# BadgeHighSchoolFirst2.net
KiCad netlist of a schematic drawn in EAGLE
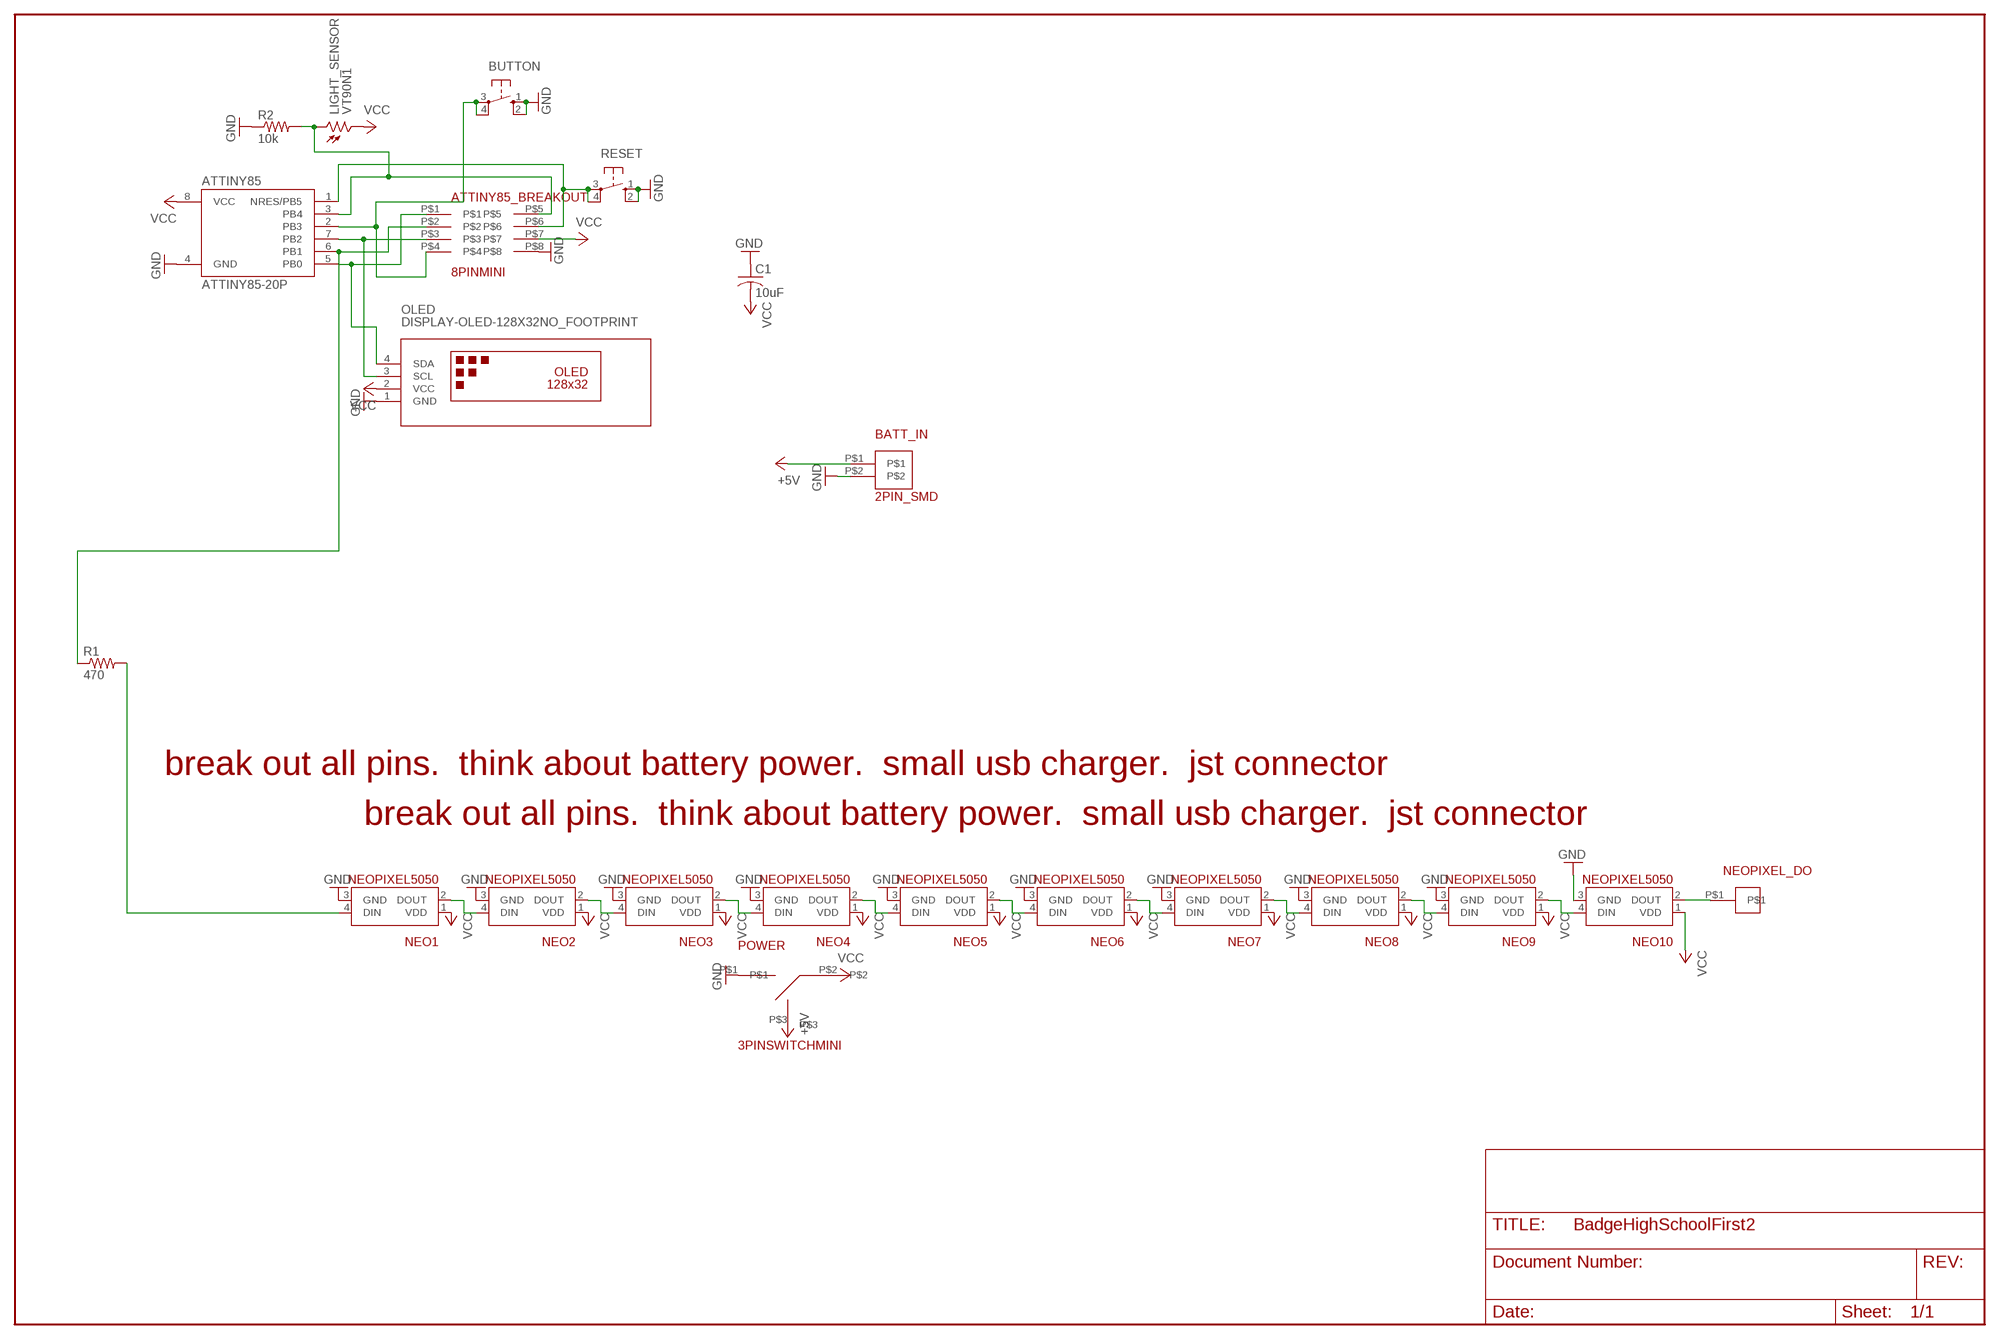
[diagram p0: schematic, sheet 1]

(export (version "E")
  (design (tool "Eeschema 10.0.6"))
  (components
    (comp (ref "ATTINY85")
      (value "ATTINY85-20P")
      (footprint "eagle-import:PDIP08_300MIL")
      (libsource (lib "eagle-import") (part "ATTINY85P-20"))
    )
    (comp (ref "ATTINY85_BREAKOUT")
      (value "8PINMINI")
      (footprint "eagle-import:8PINMINI")
      (libsource (lib "eagle-import") (part "8PINMINI"))
    )
    (comp (ref "BATT_IN")
      (value "2PIN_SMD")
      (footprint "eagle-import:2PIN_SMD")
      (libsource (lib "eagle-import") (part "2PIN_SMD"))
    )
    (comp (ref "BUTTON")
      (value "10-XX")
      (footprint "eagle-import:B3F-10XX")
      (fields (field (name "MPN") "B3F-1000"))
      (libsource (lib "eagle-import") (part "10-XX"))
    )
    (comp (ref "C1")
      (value "10uF")
      (footprint "eagle-import:C025-024X044")
      (libsource (lib "eagle-import") (part "C-US025-024X044"))
    )
    (comp (ref "LIGHT_SENSOR")
      (value "VT90N1")
      (footprint "eagle-import:VT900")
      (libsource (lib "eagle-import") (part "VT90N1"))
    )
    (comp (ref "NEO1")
      (value "NEOPIXEL5050")
      (footprint "eagle-import:NEOPIXEL5050")
      (libsource (lib "eagle-import") (part "NEOPIXEL5050"))
    )
    (comp (ref "NEO2")
      (value "NEOPIXEL5050")
      (footprint "eagle-import:NEOPIXEL5050")
      (libsource (lib "eagle-import") (part "NEOPIXEL5050"))
    )
    (comp (ref "NEO3")
      (value "NEOPIXEL5050")
      (footprint "eagle-import:NEOPIXEL5050")
      (libsource (lib "eagle-import") (part "NEOPIXEL5050"))
    )
    (comp (ref "NEO4")
      (value "NEOPIXEL5050")
      (footprint "eagle-import:NEOPIXEL5050")
      (libsource (lib "eagle-import") (part "NEOPIXEL5050"))
    )
    (comp (ref "NEO5")
      (value "NEOPIXEL5050")
      (footprint "eagle-import:NEOPIXEL5050")
      (libsource (lib "eagle-import") (part "NEOPIXEL5050"))
    )
    (comp (ref "NEO6")
      (value "NEOPIXEL5050")
      (footprint "eagle-import:NEOPIXEL5050")
      (libsource (lib "eagle-import") (part "NEOPIXEL5050"))
    )
    (comp (ref "NEO7")
      (value "NEOPIXEL5050")
      (footprint "eagle-import:NEOPIXEL5050")
      (libsource (lib "eagle-import") (part "NEOPIXEL5050"))
    )
    (comp (ref "NEO8")
      (value "NEOPIXEL5050")
      (footprint "eagle-import:NEOPIXEL5050")
      (libsource (lib "eagle-import") (part "NEOPIXEL5050"))
    )
    (comp (ref "NEO9")
      (value "NEOPIXEL5050")
      (footprint "eagle-import:NEOPIXEL5050")
      (libsource (lib "eagle-import") (part "NEOPIXEL5050"))
    )
    (comp (ref "NEO10")
      (value "NEOPIXEL5050")
      (footprint "eagle-import:NEOPIXEL5050")
      (libsource (lib "eagle-import") (part "NEOPIXEL5050"))
    )
    (comp (ref "NEOPIXEL_DO")
      (value "1PINMINI")
      (footprint "eagle-import:1PINMINI")
      (libsource (lib "eagle-import") (part "1PINMINI"))
    )
    (comp (ref "OLED")
      (value "DISPLAY-OLED-128X32NO_FOOTPRINT")
      (footprint "eagle-import:DISPLAY-OLED-128X32_NO_FOOTPRINT")
      (libsource (lib "eagle-import") (part "DISPLAY-OLED-128X32NO_FOOTPRINT"))
    )
    (comp (ref "POWER")
      (value "3PINSWITCHMINI")
      (footprint "eagle-import:3PINMINI")
      (libsource (lib "eagle-import") (part "3PINSWITCHMINI"))
    )
    (comp (ref "R1")
      (value "470")
      (footprint "eagle-import:0204_5")
      (libsource (lib "eagle-import") (part "R-US_0204/5"))
    )
    (comp (ref "R2")
      (value "10k")
      (footprint "eagle-import:0204_5")
      (libsource (lib "eagle-import") (part "R-US_0204/5"))
    )
    (comp (ref "RESET")
      (value "10-XX")
      (footprint "eagle-import:B3F-10XX")
      (fields (field (name "MPN") "B3F-1000"))
      (libsource (lib "eagle-import") (part "10-XX"))
    )
  )
  (nets
    (net (code "1") (name "+5V") (class "Default")
      (node (ref "BATT_IN") (pin "P$1") (pinfunction "P$1_P$1") (pintype "bidirectional"))
      (node (ref "POWER") (pin "P$3") (pinfunction "P$3_P$3") (pintype "bidirectional"))
    )
    (net (code "2") (name "GND") (class "Default")
      (node (ref "ATTINY85") (pin "4") (pinfunction "GND_4") (pintype "power_in"))
      (node (ref "ATTINY85_BREAKOUT") (pin "P$8") (pinfunction "P$8_P$8") (pintype "bidirectional"))
      (node (ref "BATT_IN") (pin "P$2") (pinfunction "P$2_P$2") (pintype "bidirectional"))
      (node (ref "BUTTON") (pin "1") (pinfunction "S_1") (pintype "passive"))
      (node (ref "BUTTON") (pin "2") (pinfunction "S1_2") (pintype "passive"))
      (node (ref "C1") (pin "1") (pinfunction "1_1") (pintype "passive"))
      (node (ref "NEO1") (pin "3") (pinfunction "GND_3") (pintype "bidirectional"))
      (node (ref "NEO10") (pin "3") (pinfunction "GND_3") (pintype "bidirectional"))
      (node (ref "NEO2") (pin "3") (pinfunction "GND_3") (pintype "bidirectional"))
      (node (ref "NEO3") (pin "3") (pinfunction "GND_3") (pintype "bidirectional"))
      (node (ref "NEO4") (pin "3") (pinfunction "GND_3") (pintype "bidirectional"))
      (node (ref "NEO5") (pin "3") (pinfunction "GND_3") (pintype "bidirectional"))
      (node (ref "NEO6") (pin "3") (pinfunction "GND_3") (pintype "bidirectional"))
      (node (ref "NEO7") (pin "3") (pinfunction "GND_3") (pintype "bidirectional"))
      (node (ref "NEO8") (pin "3") (pinfunction "GND_3") (pintype "bidirectional"))
      (node (ref "NEO9") (pin "3") (pinfunction "GND_3") (pintype "bidirectional"))
      (node (ref "OLED") (pin "1") (pinfunction "GND_1") (pintype "power_in"))
      (node (ref "POWER") (pin "P$1") (pinfunction "P$1_P$1") (pintype "bidirectional"))
      (node (ref "R2") (pin "1") (pinfunction "1_1") (pintype "passive"))
      (node (ref "RESET") (pin "1") (pinfunction "S_1") (pintype "passive"))
      (node (ref "RESET") (pin "2") (pinfunction "S1_2") (pintype "passive"))
    )
    (net (code "3") (name "Net-(ATTINY85-NRES{slash}PB5)") (class "Default")
      (node (ref "ATTINY85") (pin "1") (pinfunction "NRES/PB5_1") (pintype "bidirectional"))
      (node (ref "ATTINY85_BREAKOUT") (pin "P$6") (pinfunction "P$6_P$6") (pintype "bidirectional"))
      (node (ref "RESET") (pin "3") (pinfunction "P_3") (pintype "passive"))
      (node (ref "RESET") (pin "4") (pinfunction "P1_4") (pintype "passive"))
    )
    (net (code "4") (name "Net-(ATTINY85-PB0)") (class "Default")
      (node (ref "ATTINY85") (pin "5") (pinfunction "PB0_5") (pintype "bidirectional"))
      (node (ref "ATTINY85_BREAKOUT") (pin "P$1") (pinfunction "P$1_P$1") (pintype "bidirectional"))
      (node (ref "OLED") (pin "4") (pinfunction "SDA_4") (pintype "bidirectional"))
    )
    (net (code "5") (name "Net-(ATTINY85-PB1)") (class "Default")
      (node (ref "ATTINY85") (pin "6") (pinfunction "PB1_6") (pintype "bidirectional"))
      (node (ref "ATTINY85_BREAKOUT") (pin "P$2") (pinfunction "P$2_P$2") (pintype "bidirectional"))
      (node (ref "R1") (pin "1") (pinfunction "1_1") (pintype "passive"))
    )
    (net (code "6") (name "Net-(ATTINY85-PB2)") (class "Default")
      (node (ref "ATTINY85") (pin "7") (pinfunction "PB2_7") (pintype "bidirectional"))
      (node (ref "ATTINY85_BREAKOUT") (pin "P$3") (pinfunction "P$3_P$3") (pintype "bidirectional"))
      (node (ref "OLED") (pin "3") (pinfunction "SCL_3") (pintype "bidirectional"))
    )
    (net (code "7") (name "Net-(ATTINY85-PB3)") (class "Default")
      (node (ref "ATTINY85") (pin "2") (pinfunction "PB3_2") (pintype "bidirectional"))
      (node (ref "ATTINY85_BREAKOUT") (pin "P$4") (pinfunction "P$4_P$4") (pintype "bidirectional"))
      (node (ref "BUTTON") (pin "3") (pinfunction "P_3") (pintype "passive"))
      (node (ref "BUTTON") (pin "4") (pinfunction "P1_4") (pintype "passive"))
    )
    (net (code "8") (name "Net-(ATTINY85-PB4)") (class "Default")
      (node (ref "ATTINY85") (pin "3") (pinfunction "PB4_3") (pintype "bidirectional"))
      (node (ref "ATTINY85_BREAKOUT") (pin "P$5") (pinfunction "P$5_P$5") (pintype "bidirectional"))
      (node (ref "LIGHT_SENSOR") (pin "1") (pinfunction "1_1") (pintype "passive"))
      (node (ref "R2") (pin "2") (pinfunction "2_2") (pintype "passive"))
    )
    (net (code "9") (name "Net-(NEO1-DIN)") (class "Default")
      (node (ref "NEO1") (pin "4") (pinfunction "DIN_4") (pintype "bidirectional"))
      (node (ref "R1") (pin "2") (pinfunction "2_2") (pintype "passive"))
    )
    (net (code "10") (name "Net-(NEO1-DOUT)") (class "Default")
      (node (ref "NEO1") (pin "2") (pinfunction "DOUT_2") (pintype "bidirectional"))
      (node (ref "NEO2") (pin "4") (pinfunction "DIN_4") (pintype "bidirectional"))
    )
    (net (code "11") (name "Net-(NEO2-DOUT)") (class "Default")
      (node (ref "NEO2") (pin "2") (pinfunction "DOUT_2") (pintype "bidirectional"))
      (node (ref "NEO3") (pin "4") (pinfunction "DIN_4") (pintype "bidirectional"))
    )
    (net (code "12") (name "Net-(NEO3-DOUT)") (class "Default")
      (node (ref "NEO3") (pin "2") (pinfunction "DOUT_2") (pintype "bidirectional"))
      (node (ref "NEO4") (pin "4") (pinfunction "DIN_4") (pintype "bidirectional"))
    )
    (net (code "13") (name "Net-(NEO4-DOUT)") (class "Default")
      (node (ref "NEO4") (pin "2") (pinfunction "DOUT_2") (pintype "bidirectional"))
      (node (ref "NEO5") (pin "4") (pinfunction "DIN_4") (pintype "bidirectional"))
    )
    (net (code "14") (name "Net-(NEO5-DOUT)") (class "Default")
      (node (ref "NEO5") (pin "2") (pinfunction "DOUT_2") (pintype "bidirectional"))
      (node (ref "NEO6") (pin "4") (pinfunction "DIN_4") (pintype "bidirectional"))
    )
    (net (code "15") (name "Net-(NEO6-DOUT)") (class "Default")
      (node (ref "NEO6") (pin "2") (pinfunction "DOUT_2") (pintype "bidirectional"))
      (node (ref "NEO7") (pin "4") (pinfunction "DIN_4") (pintype "bidirectional"))
    )
    (net (code "16") (name "Net-(NEO7-DOUT)") (class "Default")
      (node (ref "NEO7") (pin "2") (pinfunction "DOUT_2") (pintype "bidirectional"))
      (node (ref "NEO8") (pin "4") (pinfunction "DIN_4") (pintype "bidirectional"))
    )
    (net (code "17") (name "Net-(NEO8-DOUT)") (class "Default")
      (node (ref "NEO8") (pin "2") (pinfunction "DOUT_2") (pintype "bidirectional"))
      (node (ref "NEO9") (pin "4") (pinfunction "DIN_4") (pintype "bidirectional"))
    )
    (net (code "18") (name "Net-(NEO10-DIN)") (class "Default")
      (node (ref "NEO10") (pin "4") (pinfunction "DIN_4") (pintype "bidirectional"))
      (node (ref "NEO9") (pin "2") (pinfunction "DOUT_2") (pintype "bidirectional"))
    )
    (net (code "19") (name "Net-(NEO10-DOUT)") (class "Default")
      (node (ref "NEO10") (pin "2") (pinfunction "DOUT_2") (pintype "bidirectional"))
      (node (ref "NEOPIXEL_DO") (pin "P$1") (pinfunction "P$1_P$1") (pintype "bidirectional"))
    )
    (net (code "20") (name "VCC") (class "Default")
      (node (ref "ATTINY85") (pin "8") (pinfunction "VCC_8") (pintype "power_in"))
      (node (ref "ATTINY85_BREAKOUT") (pin "P$7") (pinfunction "P$7_P$7") (pintype "bidirectional"))
      (node (ref "C1") (pin "2") (pinfunction "2_2") (pintype "passive"))
      (node (ref "LIGHT_SENSOR") (pin "2") (pinfunction "2_2") (pintype "passive"))
      (node (ref "NEO1") (pin "1") (pinfunction "VDD_1") (pintype "bidirectional"))
      (node (ref "NEO10") (pin "1") (pinfunction "VDD_1") (pintype "bidirectional"))
      (node (ref "NEO2") (pin "1") (pinfunction "VDD_1") (pintype "bidirectional"))
      (node (ref "NEO3") (pin "1") (pinfunction "VDD_1") (pintype "bidirectional"))
      (node (ref "NEO4") (pin "1") (pinfunction "VDD_1") (pintype "bidirectional"))
      (node (ref "NEO5") (pin "1") (pinfunction "VDD_1") (pintype "bidirectional"))
      (node (ref "NEO6") (pin "1") (pinfunction "VDD_1") (pintype "bidirectional"))
      (node (ref "NEO7") (pin "1") (pinfunction "VDD_1") (pintype "bidirectional"))
      (node (ref "NEO8") (pin "1") (pinfunction "VDD_1") (pintype "bidirectional"))
      (node (ref "NEO9") (pin "1") (pinfunction "VDD_1") (pintype "bidirectional"))
      (node (ref "OLED") (pin "2") (pinfunction "VCC_2") (pintype "power_in"))
      (node (ref "POWER") (pin "P$2") (pinfunction "P$2_P$2") (pintype "bidirectional"))
    )
  )
)
